# project.net
KiCad netlist of a schematic drawn in Altium Designer
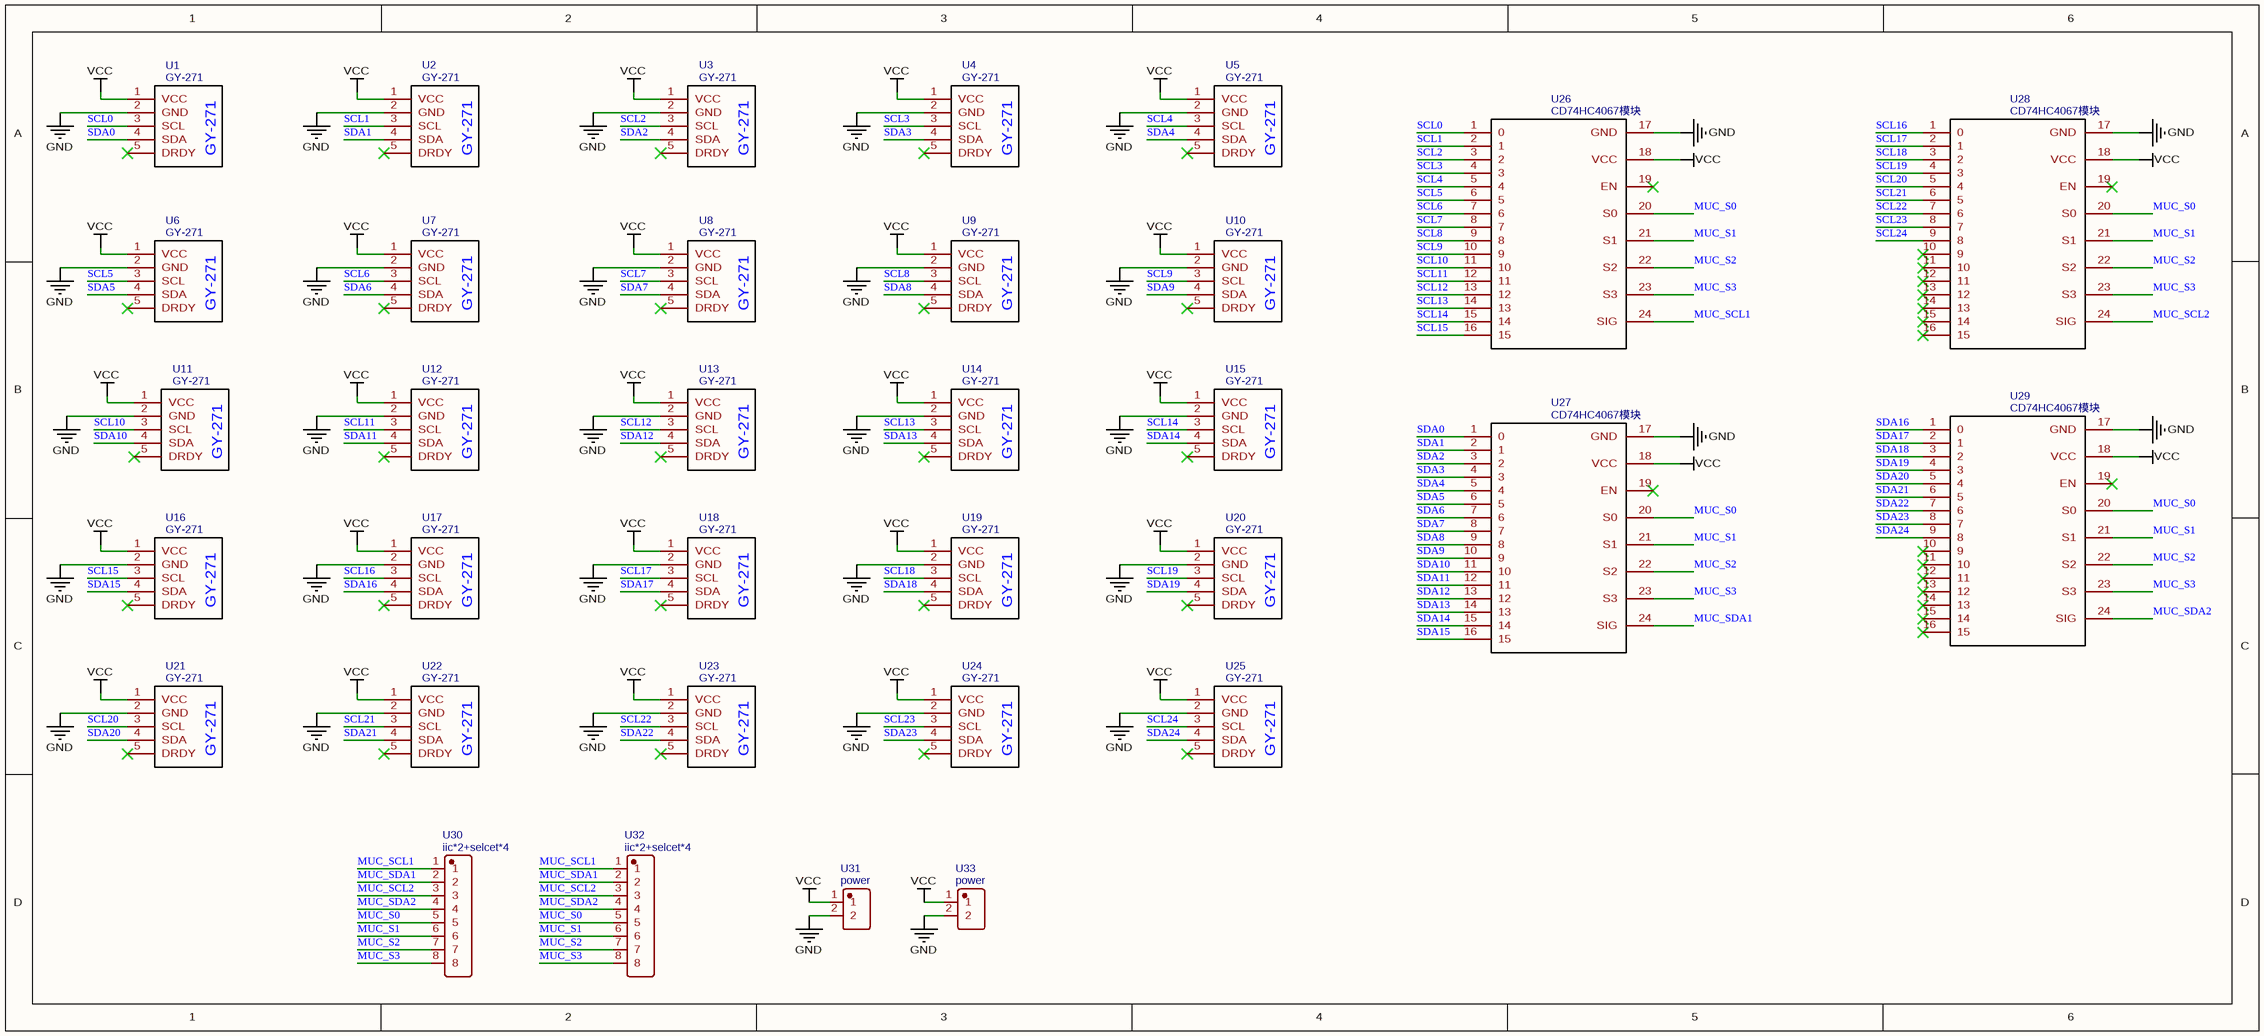
[diagram p0: project.schdoc]

(export (version "E")
  (design (tool "Eeschema 10.0.6"))
  (components
    (comp (ref "U1")
      (value "GY-271")
      (fields (field (name "CONTRIBUTOR") "shenmz"))
      (libsource (lib "altium-import") (part "root_0_GY-271_"))
    )
    (comp (ref "U2")
      (value "GY-271")
      (fields (field (name "CONTRIBUTOR") "shenmz"))
      (libsource (lib "altium-import") (part "root_0_GY-271_"))
    )
    (comp (ref "U3")
      (value "GY-271")
      (fields (field (name "CONTRIBUTOR") "shenmz"))
      (libsource (lib "altium-import") (part "root_0_GY-271_"))
    )
    (comp (ref "U4")
      (value "GY-271")
      (fields (field (name "CONTRIBUTOR") "shenmz"))
      (libsource (lib "altium-import") (part "root_0_GY-271_"))
    )
    (comp (ref "U5")
      (value "GY-271")
      (fields (field (name "CONTRIBUTOR") "shenmz"))
      (libsource (lib "altium-import") (part "root_0_GY-271_"))
    )
    (comp (ref "U6")
      (value "GY-271")
      (fields (field (name "CONTRIBUTOR") "shenmz"))
      (libsource (lib "altium-import") (part "root_0_GY-271_"))
    )
    (comp (ref "U7")
      (value "GY-271")
      (fields (field (name "CONTRIBUTOR") "shenmz"))
      (libsource (lib "altium-import") (part "root_0_GY-271_"))
    )
    (comp (ref "U8")
      (value "GY-271")
      (fields (field (name "CONTRIBUTOR") "shenmz"))
      (libsource (lib "altium-import") (part "root_0_GY-271_"))
    )
    (comp (ref "U9")
      (value "GY-271")
      (fields (field (name "CONTRIBUTOR") "shenmz"))
      (libsource (lib "altium-import") (part "root_0_GY-271_"))
    )
    (comp (ref "U10")
      (value "GY-271")
      (fields (field (name "CONTRIBUTOR") "shenmz"))
      (libsource (lib "altium-import") (part "root_0_GY-271_"))
    )
    (comp (ref "U11")
      (value "GY-271")
      (fields (field (name "CONTRIBUTOR") "shenmz"))
      (libsource (lib "altium-import") (part "root_0_GY-271_"))
    )
    (comp (ref "U12")
      (value "GY-271")
      (fields (field (name "CONTRIBUTOR") "shenmz"))
      (libsource (lib "altium-import") (part "root_0_GY-271_"))
    )
    (comp (ref "U13")
      (value "GY-271")
      (fields (field (name "CONTRIBUTOR") "shenmz"))
      (libsource (lib "altium-import") (part "root_0_GY-271_"))
    )
    (comp (ref "U14")
      (value "GY-271")
      (fields (field (name "CONTRIBUTOR") "shenmz"))
      (libsource (lib "altium-import") (part "root_0_GY-271_"))
    )
    (comp (ref "U15")
      (value "GY-271")
      (fields (field (name "CONTRIBUTOR") "shenmz"))
      (libsource (lib "altium-import") (part "root_0_GY-271_"))
    )
    (comp (ref "U16")
      (value "GY-271")
      (fields (field (name "CONTRIBUTOR") "shenmz"))
      (libsource (lib "altium-import") (part "root_0_GY-271_"))
    )
    (comp (ref "U17")
      (value "GY-271")
      (fields (field (name "CONTRIBUTOR") "shenmz"))
      (libsource (lib "altium-import") (part "root_0_GY-271_"))
    )
    (comp (ref "U18")
      (value "GY-271")
      (fields (field (name "CONTRIBUTOR") "shenmz"))
      (libsource (lib "altium-import") (part "root_0_GY-271_"))
    )
    (comp (ref "U19")
      (value "GY-271")
      (fields (field (name "CONTRIBUTOR") "shenmz"))
      (libsource (lib "altium-import") (part "root_0_GY-271_"))
    )
    (comp (ref "U20")
      (value "GY-271")
      (fields (field (name "CONTRIBUTOR") "shenmz"))
      (libsource (lib "altium-import") (part "root_0_GY-271_"))
    )
    (comp (ref "U21")
      (value "GY-271")
      (fields (field (name "CONTRIBUTOR") "shenmz"))
      (libsource (lib "altium-import") (part "root_0_GY-271_"))
    )
    (comp (ref "U22")
      (value "GY-271")
      (fields (field (name "CONTRIBUTOR") "shenmz"))
      (libsource (lib "altium-import") (part "root_0_GY-271_"))
    )
    (comp (ref "U23")
      (value "GY-271")
      (fields (field (name "CONTRIBUTOR") "shenmz"))
      (libsource (lib "altium-import") (part "root_0_GY-271_"))
    )
    (comp (ref "U24")
      (value "GY-271")
      (fields (field (name "CONTRIBUTOR") "shenmz"))
      (libsource (lib "altium-import") (part "root_0_GY-271_"))
    )
    (comp (ref "U25")
      (value "GY-271")
      (fields (field (name "CONTRIBUTOR") "shenmz"))
      (libsource (lib "altium-import") (part "root_0_GY-271_"))
    )
    (comp (ref "U26")
      (value "CD74HC4067模块")
      (fields (field (name "CONTRIBUTOR") "ShenMZ"))
      (libsource (lib "altium-import") (part "root_0_CD74HC4067模块_"))
    )
    (comp (ref "U27")
      (value "CD74HC4067模块")
      (fields (field (name "CONTRIBUTOR") "ShenMZ"))
      (libsource (lib "altium-import") (part "root_0_CD74HC4067模块_"))
    )
    (comp (ref "U28")
      (value "CD74HC4067模块")
      (fields (field (name "CONTRIBUTOR") "ShenMZ"))
      (libsource (lib "altium-import") (part "root_0_CD74HC4067模块_"))
    )
    (comp (ref "U29")
      (value "CD74HC4067模块")
      (fields (field (name "CONTRIBUTOR") "ShenMZ"))
      (libsource (lib "altium-import") (part "root_0_CD74HC4067模块_"))
    )
    (comp (ref "U30")
      (value "iic*2+selcet*4")
      (fields
        (field (name "MANUFACTURER") "Bossie(博锡)")
        (field (name "MANUFACTURER PART") "BX-PM2.54-1-8PY")
        (field (name "CONTRIBUTOR") "lcsc")
      )
      (libsource (lib "altium-import") (part "root_0_iic*2+selcet*4_"))
    )
    (comp (ref "U31")
      (value "power")
      (fields
        (field (name "MANUFACTURER") "Megastar(兆星)")
        (field (name "MANUFACTURER PART") "ZX-PZ2.54-1-2PZZ")
        (field (name "CONTRIBUTOR") "lcsc")
      )
      (libsource (lib "altium-import") (part "root_0_power_"))
    )
    (comp (ref "U32")
      (value "iic*2+selcet*4")
      (fields
        (field (name "MANUFACTURER") "Bossie(博锡)")
        (field (name "MANUFACTURER PART") "BX-PM2.54-1-8PY")
        (field (name "CONTRIBUTOR") "lcsc")
      )
      (libsource (lib "altium-import") (part "root_0_iic*2+selcet*4_"))
    )
    (comp (ref "U33")
      (value "power")
      (fields
        (field (name "MANUFACTURER") "Megastar(兆星)")
        (field (name "MANUFACTURER PART") "ZX-PZ2.54-1-2PZZ")
        (field (name "CONTRIBUTOR") "lcsc")
      )
      (libsource (lib "altium-import") (part "root_0_power_"))
    )
  )
  (nets
    (net (code "1") (name "/MUC_S0") (class "Default")
      (node (ref "U26") (pin "20") (pinfunction "S0_20") (pintype "passive"))
      (node (ref "U27") (pin "20") (pinfunction "S0_20") (pintype "passive"))
      (node (ref "U28") (pin "20") (pinfunction "S0_20") (pintype "passive"))
      (node (ref "U29") (pin "20") (pinfunction "S0_20") (pintype "passive"))
      (node (ref "U30") (pin "5") (pinfunction "5_5") (pintype "passive"))
      (node (ref "U32") (pin "5") (pinfunction "5_5") (pintype "passive"))
    )
    (net (code "2") (name "/MUC_S1") (class "Default")
      (node (ref "U26") (pin "21") (pinfunction "S1_21") (pintype "passive"))
      (node (ref "U27") (pin "21") (pinfunction "S1_21") (pintype "passive"))
      (node (ref "U28") (pin "21") (pinfunction "S1_21") (pintype "passive"))
      (node (ref "U29") (pin "21") (pinfunction "S1_21") (pintype "passive"))
      (node (ref "U30") (pin "6") (pinfunction "6_6") (pintype "passive"))
      (node (ref "U32") (pin "6") (pinfunction "6_6") (pintype "passive"))
    )
    (net (code "3") (name "/MUC_S2") (class "Default")
      (node (ref "U26") (pin "22") (pinfunction "S2_22") (pintype "passive"))
      (node (ref "U27") (pin "22") (pinfunction "S2_22") (pintype "passive"))
      (node (ref "U28") (pin "22") (pinfunction "S2_22") (pintype "passive"))
      (node (ref "U29") (pin "22") (pinfunction "S2_22") (pintype "passive"))
      (node (ref "U30") (pin "7") (pinfunction "7_7") (pintype "passive"))
      (node (ref "U32") (pin "7") (pinfunction "7_7") (pintype "passive"))
    )
    (net (code "4") (name "/MUC_S3") (class "Default")
      (node (ref "U26") (pin "23") (pinfunction "S3_23") (pintype "passive"))
      (node (ref "U27") (pin "23") (pinfunction "S3_23") (pintype "passive"))
      (node (ref "U28") (pin "23") (pinfunction "S3_23") (pintype "passive"))
      (node (ref "U29") (pin "23") (pinfunction "S3_23") (pintype "passive"))
      (node (ref "U30") (pin "8") (pinfunction "8_8") (pintype "passive"))
      (node (ref "U32") (pin "8") (pinfunction "8_8") (pintype "passive"))
    )
    (net (code "5") (name "/MUC_SCL1") (class "Default")
      (node (ref "U26") (pin "24") (pinfunction "SIG_24") (pintype "passive"))
      (node (ref "U30") (pin "1") (pinfunction "1_1") (pintype "passive"))
      (node (ref "U32") (pin "1") (pinfunction "1_1") (pintype "passive"))
    )
    (net (code "6") (name "/MUC_SCL2") (class "Default")
      (node (ref "U28") (pin "24") (pinfunction "SIG_24") (pintype "passive"))
      (node (ref "U30") (pin "3") (pinfunction "3_3") (pintype "passive"))
      (node (ref "U32") (pin "3") (pinfunction "3_3") (pintype "passive"))
    )
    (net (code "7") (name "/MUC_SDA1") (class "Default")
      (node (ref "U27") (pin "24") (pinfunction "SIG_24") (pintype "passive"))
      (node (ref "U30") (pin "2") (pinfunction "2_2") (pintype "passive"))
      (node (ref "U32") (pin "2") (pinfunction "2_2") (pintype "passive"))
    )
    (net (code "8") (name "/MUC_SDA2") (class "Default")
      (node (ref "U29") (pin "24") (pinfunction "SIG_24") (pintype "passive"))
      (node (ref "U30") (pin "4") (pinfunction "4_4") (pintype "passive"))
      (node (ref "U32") (pin "4") (pinfunction "4_4") (pintype "passive"))
    )
    (net (code "9") (name "/SCL0") (class "Default")
      (node (ref "U1") (pin "3") (pinfunction "SCL_3") (pintype "passive"))
      (node (ref "U26") (pin "1") (pinfunction "0_1") (pintype "passive"))
    )
    (net (code "10") (name "/SCL1") (class "Default")
      (node (ref "U2") (pin "3") (pinfunction "SCL_3") (pintype "passive"))
      (node (ref "U26") (pin "2") (pinfunction "1_2") (pintype "passive"))
    )
    (net (code "11") (name "/SCL2") (class "Default")
      (node (ref "U26") (pin "3") (pinfunction "2_3") (pintype "passive"))
      (node (ref "U3") (pin "3") (pinfunction "SCL_3") (pintype "passive"))
    )
    (net (code "12") (name "/SCL3") (class "Default")
      (node (ref "U26") (pin "4") (pinfunction "3_4") (pintype "passive"))
      (node (ref "U4") (pin "3") (pinfunction "SCL_3") (pintype "passive"))
    )
    (net (code "13") (name "/SCL4") (class "Default")
      (node (ref "U26") (pin "5") (pinfunction "4_5") (pintype "passive"))
      (node (ref "U5") (pin "3") (pinfunction "SCL_3") (pintype "passive"))
    )
    (net (code "14") (name "/SCL5") (class "Default")
      (node (ref "U26") (pin "6") (pinfunction "5_6") (pintype "passive"))
      (node (ref "U6") (pin "3") (pinfunction "SCL_3") (pintype "passive"))
    )
    (net (code "15") (name "/SCL6") (class "Default")
      (node (ref "U26") (pin "7") (pinfunction "6_7") (pintype "passive"))
      (node (ref "U7") (pin "3") (pinfunction "SCL_3") (pintype "passive"))
    )
    (net (code "16") (name "/SCL7") (class "Default")
      (node (ref "U26") (pin "8") (pinfunction "7_8") (pintype "passive"))
      (node (ref "U8") (pin "3") (pinfunction "SCL_3") (pintype "passive"))
    )
    (net (code "17") (name "/SCL8") (class "Default")
      (node (ref "U26") (pin "9") (pinfunction "8_9") (pintype "passive"))
      (node (ref "U9") (pin "3") (pinfunction "SCL_3") (pintype "passive"))
    )
    (net (code "18") (name "/SCL9") (class "Default")
      (node (ref "U10") (pin "3") (pinfunction "SCL_3") (pintype "passive"))
      (node (ref "U26") (pin "10") (pinfunction "9_10") (pintype "passive"))
    )
    (net (code "19") (name "/SCL10") (class "Default")
      (node (ref "U11") (pin "3") (pinfunction "SCL_3") (pintype "passive"))
      (node (ref "U26") (pin "11") (pinfunction "10_11") (pintype "passive"))
    )
    (net (code "20") (name "/SCL11") (class "Default")
      (node (ref "U12") (pin "3") (pinfunction "SCL_3") (pintype "passive"))
      (node (ref "U26") (pin "12") (pinfunction "11_12") (pintype "passive"))
    )
    (net (code "21") (name "/SCL12") (class "Default")
      (node (ref "U13") (pin "3") (pinfunction "SCL_3") (pintype "passive"))
      (node (ref "U26") (pin "13") (pinfunction "12_13") (pintype "passive"))
    )
    (net (code "22") (name "/SCL13") (class "Default")
      (node (ref "U14") (pin "3") (pinfunction "SCL_3") (pintype "passive"))
      (node (ref "U26") (pin "14") (pinfunction "13_14") (pintype "passive"))
    )
    (net (code "23") (name "/SCL14") (class "Default")
      (node (ref "U15") (pin "3") (pinfunction "SCL_3") (pintype "passive"))
      (node (ref "U26") (pin "15") (pinfunction "14_15") (pintype "passive"))
    )
    (net (code "24") (name "/SCL15") (class "Default")
      (node (ref "U16") (pin "3") (pinfunction "SCL_3") (pintype "passive"))
      (node (ref "U26") (pin "16") (pinfunction "15_16") (pintype "passive"))
    )
    (net (code "25") (name "/SCL16") (class "Default")
      (node (ref "U17") (pin "3") (pinfunction "SCL_3") (pintype "passive"))
      (node (ref "U28") (pin "1") (pinfunction "0_1") (pintype "passive"))
    )
    (net (code "26") (name "/SCL17") (class "Default")
      (node (ref "U18") (pin "3") (pinfunction "SCL_3") (pintype "passive"))
      (node (ref "U28") (pin "2") (pinfunction "1_2") (pintype "passive"))
    )
    (net (code "27") (name "/SCL18") (class "Default")
      (node (ref "U19") (pin "3") (pinfunction "SCL_3") (pintype "passive"))
      (node (ref "U28") (pin "3") (pinfunction "2_3") (pintype "passive"))
    )
    (net (code "28") (name "/SCL19") (class "Default")
      (node (ref "U20") (pin "3") (pinfunction "SCL_3") (pintype "passive"))
      (node (ref "U28") (pin "4") (pinfunction "3_4") (pintype "passive"))
    )
    (net (code "29") (name "/SCL20") (class "Default")
      (node (ref "U21") (pin "3") (pinfunction "SCL_3") (pintype "passive"))
      (node (ref "U28") (pin "5") (pinfunction "4_5") (pintype "passive"))
    )
    (net (code "30") (name "/SCL21") (class "Default")
      (node (ref "U22") (pin "3") (pinfunction "SCL_3") (pintype "passive"))
      (node (ref "U28") (pin "6") (pinfunction "5_6") (pintype "passive"))
    )
    (net (code "31") (name "/SCL22") (class "Default")
      (node (ref "U23") (pin "3") (pinfunction "SCL_3") (pintype "passive"))
      (node (ref "U28") (pin "7") (pinfunction "6_7") (pintype "passive"))
    )
    (net (code "32") (name "/SCL23") (class "Default")
      (node (ref "U24") (pin "3") (pinfunction "SCL_3") (pintype "passive"))
      (node (ref "U28") (pin "8") (pinfunction "7_8") (pintype "passive"))
    )
    (net (code "33") (name "/SCL24") (class "Default")
      (node (ref "U25") (pin "3") (pinfunction "SCL_3") (pintype "passive"))
      (node (ref "U28") (pin "9") (pinfunction "8_9") (pintype "passive"))
    )
    (net (code "34") (name "/SDA0") (class "Default")
      (node (ref "U1") (pin "4") (pinfunction "SDA_4") (pintype "passive"))
      (node (ref "U27") (pin "1") (pinfunction "0_1") (pintype "passive"))
    )
    (net (code "35") (name "/SDA1") (class "Default")
      (node (ref "U2") (pin "4") (pinfunction "SDA_4") (pintype "passive"))
      (node (ref "U27") (pin "2") (pinfunction "1_2") (pintype "passive"))
    )
    (net (code "36") (name "/SDA2") (class "Default")
      (node (ref "U27") (pin "3") (pinfunction "2_3") (pintype "passive"))
      (node (ref "U3") (pin "4") (pinfunction "SDA_4") (pintype "passive"))
    )
    (net (code "37") (name "/SDA3") (class "Default")
      (node (ref "U27") (pin "4") (pinfunction "3_4") (pintype "passive"))
      (node (ref "U4") (pin "4") (pinfunction "SDA_4") (pintype "passive"))
    )
    (net (code "38") (name "/SDA4") (class "Default")
      (node (ref "U27") (pin "5") (pinfunction "4_5") (pintype "passive"))
      (node (ref "U5") (pin "4") (pinfunction "SDA_4") (pintype "passive"))
    )
    (net (code "39") (name "/SDA5") (class "Default")
      (node (ref "U27") (pin "6") (pinfunction "5_6") (pintype "passive"))
      (node (ref "U6") (pin "4") (pinfunction "SDA_4") (pintype "passive"))
    )
    (net (code "40") (name "/SDA6") (class "Default")
      (node (ref "U27") (pin "7") (pinfunction "6_7") (pintype "passive"))
      (node (ref "U7") (pin "4") (pinfunction "SDA_4") (pintype "passive"))
    )
    (net (code "41") (name "/SDA7") (class "Default")
      (node (ref "U27") (pin "8") (pinfunction "7_8") (pintype "passive"))
      (node (ref "U8") (pin "4") (pinfunction "SDA_4") (pintype "passive"))
    )
    (net (code "42") (name "/SDA8") (class "Default")
      (node (ref "U27") (pin "9") (pinfunction "8_9") (pintype "passive"))
      (node (ref "U9") (pin "4") (pinfunction "SDA_4") (pintype "passive"))
    )
    (net (code "43") (name "/SDA9") (class "Default")
      (node (ref "U10") (pin "4") (pinfunction "SDA_4") (pintype "passive"))
      (node (ref "U27") (pin "10") (pinfunction "9_10") (pintype "passive"))
    )
    (net (code "44") (name "/SDA10") (class "Default")
      (node (ref "U11") (pin "4") (pinfunction "SDA_4") (pintype "passive"))
      (node (ref "U27") (pin "11") (pinfunction "10_11") (pintype "passive"))
    )
    (net (code "45") (name "/SDA11") (class "Default")
      (node (ref "U12") (pin "4") (pinfunction "SDA_4") (pintype "passive"))
      (node (ref "U27") (pin "12") (pinfunction "11_12") (pintype "passive"))
    )
    (net (code "46") (name "/SDA12") (class "Default")
      (node (ref "U13") (pin "4") (pinfunction "SDA_4") (pintype "passive"))
      (node (ref "U27") (pin "13") (pinfunction "12_13") (pintype "passive"))
    )
    (net (code "47") (name "/SDA13") (class "Default")
      (node (ref "U14") (pin "4") (pinfunction "SDA_4") (pintype "passive"))
      (node (ref "U27") (pin "14") (pinfunction "13_14") (pintype "passive"))
    )
    (net (code "48") (name "/SDA14") (class "Default")
      (node (ref "U15") (pin "4") (pinfunction "SDA_4") (pintype "passive"))
      (node (ref "U27") (pin "15") (pinfunction "14_15") (pintype "passive"))
    )
    (net (code "49") (name "/SDA15") (class "Default")
      (node (ref "U16") (pin "4") (pinfunction "SDA_4") (pintype "passive"))
      (node (ref "U27") (pin "16") (pinfunction "15_16") (pintype "passive"))
    )
    (net (code "50") (name "/SDA16") (class "Default")
      (node (ref "U17") (pin "4") (pinfunction "SDA_4") (pintype "passive"))
      (node (ref "U29") (pin "1") (pinfunction "0_1") (pintype "passive"))
    )
    (net (code "51") (name "/SDA17") (class "Default")
      (node (ref "U18") (pin "4") (pinfunction "SDA_4") (pintype "passive"))
      (node (ref "U29") (pin "2") (pinfunction "1_2") (pintype "passive"))
    )
    (net (code "52") (name "/SDA18") (class "Default")
      (node (ref "U19") (pin "4") (pinfunction "SDA_4") (pintype "passive"))
      (node (ref "U29") (pin "3") (pinfunction "2_3") (pintype "passive"))
    )
    (net (code "53") (name "/SDA19") (class "Default")
      (node (ref "U20") (pin "4") (pinfunction "SDA_4") (pintype "passive"))
      (node (ref "U29") (pin "4") (pinfunction "3_4") (pintype "passive"))
    )
    (net (code "54") (name "/SDA20") (class "Default")
      (node (ref "U21") (pin "4") (pinfunction "SDA_4") (pintype "passive"))
      (node (ref "U29") (pin "5") (pinfunction "4_5") (pintype "passive"))
    )
    (net (code "55") (name "/SDA21") (class "Default")
      (node (ref "U22") (pin "4") (pinfunction "SDA_4") (pintype "passive"))
      (node (ref "U29") (pin "6") (pinfunction "5_6") (pintype "passive"))
    )
    (net (code "56") (name "/SDA22") (class "Default")
      (node (ref "U23") (pin "4") (pinfunction "SDA_4") (pintype "passive"))
      (node (ref "U29") (pin "7") (pinfunction "6_7") (pintype "passive"))
    )
    (net (code "57") (name "/SDA23") (class "Default")
      (node (ref "U24") (pin "4") (pinfunction "SDA_4") (pintype "passive"))
      (node (ref "U29") (pin "8") (pinfunction "7_8") (pintype "passive"))
    )
    (net (code "58") (name "/SDA24") (class "Default")
      (node (ref "U25") (pin "4") (pinfunction "SDA_4") (pintype "passive"))
      (node (ref "U29") (pin "9") (pinfunction "8_9") (pintype "passive"))
    )
    (net (code "59") (name "GND") (class "Default")
      (node (ref "U1") (pin "2") (pinfunction "GND_2") (pintype "passive"))
      (node (ref "U10") (pin "2") (pinfunction "GND_2") (pintype "passive"))
      (node (ref "U11") (pin "2") (pinfunction "GND_2") (pintype "passive"))
      (node (ref "U12") (pin "2") (pinfunction "GND_2") (pintype "passive"))
      (node (ref "U13") (pin "2") (pinfunction "GND_2") (pintype "passive"))
      (node (ref "U14") (pin "2") (pinfunction "GND_2") (pintype "passive"))
      (node (ref "U15") (pin "2") (pinfunction "GND_2") (pintype "passive"))
      (node (ref "U16") (pin "2") (pinfunction "GND_2") (pintype "passive"))
      (node (ref "U17") (pin "2") (pinfunction "GND_2") (pintype "passive"))
      (node (ref "U18") (pin "2") (pinfunction "GND_2") (pintype "passive"))
      (node (ref "U19") (pin "2") (pinfunction "GND_2") (pintype "passive"))
      (node (ref "U2") (pin "2") (pinfunction "GND_2") (pintype "passive"))
      (node (ref "U20") (pin "2") (pinfunction "GND_2") (pintype "passive"))
      (node (ref "U21") (pin "2") (pinfunction "GND_2") (pintype "passive"))
      (node (ref "U22") (pin "2") (pinfunction "GND_2") (pintype "passive"))
      (node (ref "U23") (pin "2") (pinfunction "GND_2") (pintype "passive"))
      (node (ref "U24") (pin "2") (pinfunction "GND_2") (pintype "passive"))
      (node (ref "U25") (pin "2") (pinfunction "GND_2") (pintype "passive"))
      (node (ref "U26") (pin "17") (pinfunction "GND_17") (pintype "passive"))
      (node (ref "U27") (pin "17") (pinfunction "GND_17") (pintype "passive"))
      (node (ref "U28") (pin "17") (pinfunction "GND_17") (pintype "passive"))
      (node (ref "U29") (pin "17") (pinfunction "GND_17") (pintype "passive"))
      (node (ref "U3") (pin "2") (pinfunction "GND_2") (pintype "passive"))
      (node (ref "U31") (pin "2") (pinfunction "2_2") (pintype "passive"))
      (node (ref "U33") (pin "2") (pinfunction "2_2") (pintype "passive"))
      (node (ref "U4") (pin "2") (pinfunction "GND_2") (pintype "passive"))
      (node (ref "U5") (pin "2") (pinfunction "GND_2") (pintype "passive"))
      (node (ref "U6") (pin "2") (pinfunction "GND_2") (pintype "passive"))
      (node (ref "U7") (pin "2") (pinfunction "GND_2") (pintype "passive"))
      (node (ref "U8") (pin "2") (pinfunction "GND_2") (pintype "passive"))
      (node (ref "U9") (pin "2") (pinfunction "GND_2") (pintype "passive"))
    )
    (net (code "60") (name "VCC") (class "Default")
      (node (ref "U1") (pin "1") (pinfunction "VCC_1") (pintype "passive"))
      (node (ref "U10") (pin "1") (pinfunction "VCC_1") (pintype "passive"))
      (node (ref "U11") (pin "1") (pinfunction "VCC_1") (pintype "passive"))
      (node (ref "U12") (pin "1") (pinfunction "VCC_1") (pintype "passive"))
      (node (ref "U13") (pin "1") (pinfunction "VCC_1") (pintype "passive"))
      (node (ref "U14") (pin "1") (pinfunction "VCC_1") (pintype "passive"))
      (node (ref "U15") (pin "1") (pinfunction "VCC_1") (pintype "passive"))
      (node (ref "U16") (pin "1") (pinfunction "VCC_1") (pintype "passive"))
      (node (ref "U17") (pin "1") (pinfunction "VCC_1") (pintype "passive"))
      (node (ref "U18") (pin "1") (pinfunction "VCC_1") (pintype "passive"))
      (node (ref "U19") (pin "1") (pinfunction "VCC_1") (pintype "passive"))
      (node (ref "U2") (pin "1") (pinfunction "VCC_1") (pintype "passive"))
      (node (ref "U20") (pin "1") (pinfunction "VCC_1") (pintype "passive"))
      (node (ref "U21") (pin "1") (pinfunction "VCC_1") (pintype "passive"))
      (node (ref "U22") (pin "1") (pinfunction "VCC_1") (pintype "passive"))
      (node (ref "U23") (pin "1") (pinfunction "VCC_1") (pintype "passive"))
      (node (ref "U24") (pin "1") (pinfunction "VCC_1") (pintype "passive"))
      (node (ref "U25") (pin "1") (pinfunction "VCC_1") (pintype "passive"))
      (node (ref "U26") (pin "18") (pinfunction "VCC_18") (pintype "passive"))
      (node (ref "U27") (pin "18") (pinfunction "VCC_18") (pintype "passive"))
      (node (ref "U28") (pin "18") (pinfunction "VCC_18") (pintype "passive"))
      (node (ref "U29") (pin "18") (pinfunction "VCC_18") (pintype "passive"))
      (node (ref "U3") (pin "1") (pinfunction "VCC_1") (pintype "passive"))
      (node (ref "U31") (pin "1") (pinfunction "1_1") (pintype "passive"))
      (node (ref "U33") (pin "1") (pinfunction "1_1") (pintype "passive"))
      (node (ref "U4") (pin "1") (pinfunction "VCC_1") (pintype "passive"))
      (node (ref "U5") (pin "1") (pinfunction "VCC_1") (pintype "passive"))
      (node (ref "U6") (pin "1") (pinfunction "VCC_1") (pintype "passive"))
      (node (ref "U7") (pin "1") (pinfunction "VCC_1") (pintype "passive"))
      (node (ref "U8") (pin "1") (pinfunction "VCC_1") (pintype "passive"))
      (node (ref "U9") (pin "1") (pinfunction "VCC_1") (pintype "passive"))
    )
    (net (code "61") (name "unconnected-(U1-DRDY-Pad5)") (class "Default")
      (node (ref "U1") (pin "5") (pinfunction "DRDY_5") (pintype "passive+no_connect"))
    )
    (net (code "62") (name "unconnected-(U2-DRDY-Pad5)") (class "Default")
      (node (ref "U2") (pin "5") (pinfunction "DRDY_5") (pintype "passive+no_connect"))
    )
    (net (code "63") (name "unconnected-(U3-DRDY-Pad5)") (class "Default")
      (node (ref "U3") (pin "5") (pinfunction "DRDY_5") (pintype "passive+no_connect"))
    )
    (net (code "64") (name "unconnected-(U4-DRDY-Pad5)") (class "Default")
      (node (ref "U4") (pin "5") (pinfunction "DRDY_5") (pintype "passive+no_connect"))
    )
    (net (code "65") (name "unconnected-(U5-DRDY-Pad5)") (class "Default")
      (node (ref "U5") (pin "5") (pinfunction "DRDY_5") (pintype "passive+no_connect"))
    )
    (net (code "66") (name "unconnected-(U6-DRDY-Pad5)") (class "Default")
      (node (ref "U6") (pin "5") (pinfunction "DRDY_5") (pintype "passive+no_connect"))
    )
    (net (code "67") (name "unconnected-(U7-DRDY-Pad5)") (class "Default")
      (node (ref "U7") (pin "5") (pinfunction "DRDY_5") (pintype "passive+no_connect"))
    )
    (net (code "68") (name "unconnected-(U8-DRDY-Pad5)") (class "Default")
      (node (ref "U8") (pin "5") (pinfunction "DRDY_5") (pintype "passive+no_connect"))
    )
    (net (code "69") (name "unconnected-(U9-DRDY-Pad5)") (class "Default")
      (node (ref "U9") (pin "5") (pinfunction "DRDY_5") (pintype "passive+no_connect"))
    )
    (net (code "70") (name "unconnected-(U10-DRDY-Pad5)") (class "Default")
      (node (ref "U10") (pin "5") (pinfunction "DRDY_5") (pintype "passive+no_connect"))
    )
    (net (code "71") (name "unconnected-(U11-DRDY-Pad5)") (class "Default")
      (node (ref "U11") (pin "5") (pinfunction "DRDY_5") (pintype "passive+no_connect"))
    )
    (net (code "72") (name "unconnected-(U12-DRDY-Pad5)") (class "Default")
      (node (ref "U12") (pin "5") (pinfunction "DRDY_5") (pintype "passive+no_connect"))
    )
    (net (code "73") (name "unconnected-(U13-DRDY-Pad5)") (class "Default")
      (node (ref "U13") (pin "5") (pinfunction "DRDY_5") (pintype "passive+no_connect"))
    )
    (net (code "74") (name "unconnected-(U14-DRDY-Pad5)") (class "Default")
      (node (ref "U14") (pin "5") (pinfunction "DRDY_5") (pintype "passive+no_connect"))
    )
    (net (code "75") (name "unconnected-(U15-DRDY-Pad5)") (class "Default")
      (node (ref "U15") (pin "5") (pinfunction "DRDY_5") (pintype "passive+no_connect"))
    )
    (net (code "76") (name "unconnected-(U16-DRDY-Pad5)") (class "Default")
      (node (ref "U16") (pin "5") (pinfunction "DRDY_5") (pintype "passive+no_connect"))
    )
    (net (code "77") (name "unconnected-(U17-DRDY-Pad5)") (class "Default")
      (node (ref "U17") (pin "5") (pinfunction "DRDY_5") (pintype "passive+no_connect"))
    )
    (net (code "78") (name "unconnected-(U18-DRDY-Pad5)") (class "Default")
      (node (ref "U18") (pin "5") (pinfunction "DRDY_5") (pintype "passive+no_connect"))
    )
    (net (code "79") (name "unconnected-(U19-DRDY-Pad5)") (class "Default")
      (node (ref "U19") (pin "5") (pinfunction "DRDY_5") (pintype "passive+no_connect"))
    )
    (net (code "80") (name "unconnected-(U20-DRDY-Pad5)") (class "Default")
      (node (ref "U20") (pin "5") (pinfunction "DRDY_5") (pintype "passive+no_connect"))
    )
    (net (code "81") (name "unconnected-(U21-DRDY-Pad5)") (class "Default")
      (node (ref "U21") (pin "5") (pinfunction "DRDY_5") (pintype "passive+no_connect"))
    )
    (net (code "82") (name "unconnected-(U22-DRDY-Pad5)") (class "Default")
      (node (ref "U22") (pin "5") (pinfunction "DRDY_5") (pintype "passive+no_connect"))
    )
    (net (code "83") (name "unconnected-(U23-DRDY-Pad5)") (class "Default")
      (node (ref "U23") (pin "5") (pinfunction "DRDY_5") (pintype "passive+no_connect"))
    )
    (net (code "84") (name "unconnected-(U24-DRDY-Pad5)") (class "Default")
      (node (ref "U24") (pin "5") (pinfunction "DRDY_5") (pintype "passive+no_connect"))
    )
    (net (code "85") (name "unconnected-(U25-DRDY-Pad5)") (class "Default")
      (node (ref "U25") (pin "5") (pinfunction "DRDY_5") (pintype "passive+no_connect"))
    )
    (net (code "86") (name "unconnected-(U26-EN-Pad19)") (class "Default")
      (node (ref "U26") (pin "19") (pinfunction "EN_19") (pintype "passive+no_connect"))
    )
    (net (code "87") (name "unconnected-(U27-EN-Pad19)") (class "Default")
      (node (ref "U27") (pin "19") (pinfunction "EN_19") (pintype "passive+no_connect"))
    )
    (net (code "88") (name "unconnected-(U28-9-Pad10)") (class "Default")
      (node (ref "U28") (pin "10") (pinfunction "9_10") (pintype "passive+no_connect"))
    )
    (net (code "89") (name "unconnected-(U28-10-Pad11)") (class "Default")
      (node (ref "U28") (pin "11") (pinfunction "10_11") (pintype "passive+no_connect"))
    )
    (net (code "90") (name "unconnected-(U28-11-Pad12)") (class "Default")
      (node (ref "U28") (pin "12") (pinfunction "11_12") (pintype "passive+no_connect"))
    )
    (net (code "91") (name "unconnected-(U28-12-Pad13)") (class "Default")
      (node (ref "U28") (pin "13") (pinfunction "12_13") (pintype "passive+no_connect"))
    )
    (net (code "92") (name "unconnected-(U28-13-Pad14)") (class "Default")
      (node (ref "U28") (pin "14") (pinfunction "13_14") (pintype "passive+no_connect"))
    )
    (net (code "93") (name "unconnected-(U28-14-Pad15)") (class "Default")
      (node (ref "U28") (pin "15") (pinfunction "14_15") (pintype "passive+no_connect"))
    )
    (net (code "94") (name "unconnected-(U28-15-Pad16)") (class "Default")
      (node (ref "U28") (pin "16") (pinfunction "15_16") (pintype "passive+no_connect"))
    )
    (net (code "95") (name "unconnected-(U28-EN-Pad19)") (class "Default")
      (node (ref "U28") (pin "19") (pinfunction "EN_19") (pintype "passive+no_connect"))
    )
    (net (code "96") (name "unconnected-(U29-9-Pad10)") (class "Default")
      (node (ref "U29") (pin "10") (pinfunction "9_10") (pintype "passive+no_connect"))
    )
    (net (code "97") (name "unconnected-(U29-10-Pad11)") (class "Default")
      (node (ref "U29") (pin "11") (pinfunction "10_11") (pintype "passive+no_connect"))
    )
    (net (code "98") (name "unconnected-(U29-11-Pad12)") (class "Default")
      (node (ref "U29") (pin "12") (pinfunction "11_12") (pintype "passive+no_connect"))
    )
    (net (code "99") (name "unconnected-(U29-12-Pad13)") (class "Default")
      (node (ref "U29") (pin "13") (pinfunction "12_13") (pintype "passive+no_connect"))
    )
    (net (code "100") (name "unconnected-(U29-13-Pad14)") (class "Default")
      (node (ref "U29") (pin "14") (pinfunction "13_14") (pintype "passive+no_connect"))
    )
    (net (code "101") (name "unconnected-(U29-14-Pad15)") (class "Default")
      (node (ref "U29") (pin "15") (pinfunction "14_15") (pintype "passive+no_connect"))
    )
    (net (code "102") (name "unconnected-(U29-15-Pad16)") (class "Default")
      (node (ref "U29") (pin "16") (pinfunction "15_16") (pintype "passive+no_connect"))
    )
    (net (code "103") (name "unconnected-(U29-EN-Pad19)") (class "Default")
      (node (ref "U29") (pin "19") (pinfunction "EN_19") (pintype "passive+no_connect"))
    )
  )
)
